# McPiFace-60mmFan-V1.net
KiCad netlist of a schematic drawn in EAGLE
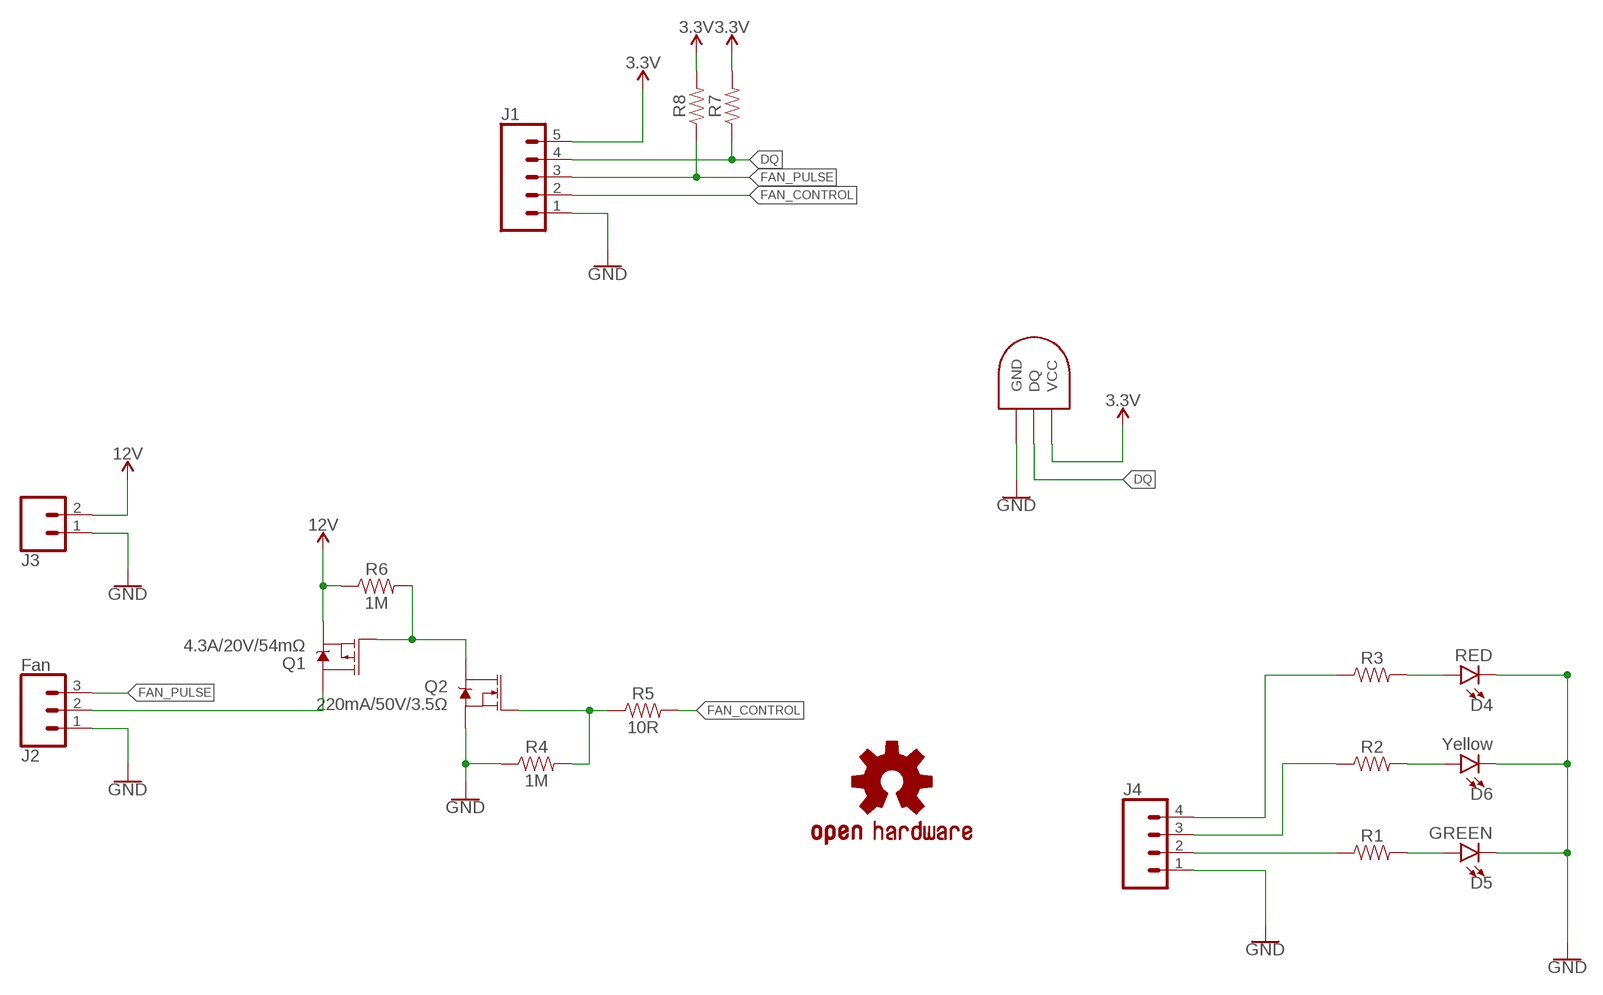
[diagram p0: schematic, sheet 1]

(export (version "E")
  (design (tool "Eeschema 10.0.6"))
  (components
    (comp (ref "D4")
      (value "RED")
      (footprint "eagle-import:LED-1206")
      (libsource (lib "eagle-import") (part "LED-RED1206"))
    )
    (comp (ref "D5")
      (value "GREEN")
      (footprint "eagle-import:LED-1206")
      (libsource (lib "eagle-import") (part "LED-GREEN1206"))
    )
    (comp (ref "D6")
      (value "Yellow")
      (footprint "eagle-import:LED-1206")
      (libsource (lib "eagle-import") (part "LED-YELLOWLILYPAD"))
    )
    (comp (ref "J1")
      (value "CONN_05SMD")
      (footprint "eagle-import:1X05_1MM")
      (libsource (lib "eagle-import") (part "CONN_05SMD"))
    )
    (comp (ref "J2")
      (value "Fan")
      (footprint "eagle-import:JST-3-SMD")
      (libsource (lib "eagle-import") (part "CONN_03JST-SMD"))
    )
    (comp (ref "J3")
      (value "CONN_02-JST-2MM-SMT")
      (footprint "eagle-import:JST-2-SMD")
      (libsource (lib "eagle-import") (part "CONN_02-JST-2MM-SMT"))
    )
    (comp (ref "J4")
      (value "CONN_04SMD2")
      (footprint "eagle-import:1X04_1MM_RA")
      (libsource (lib "eagle-import") (part "CONN_04SMD2"))
    )
    (comp (ref "LOGO1")
      (value "OSHW-LOGOL")
      (footprint "eagle-import:OSHW-LOGO-L")
      (libsource (lib "eagle-import") (part "OSHW-LOGOL"))
    )
    (comp (ref "Q1")
      (value "4.3A/20V/54mΩ")
      (footprint "eagle-import:SOT23-3")
      (libsource (lib "eagle-import") (part "MOSFET_PCH-IRLML2244"))
    )
    (comp (ref "Q2")
      (value "220mA/50V/3.5Ω")
      (footprint "eagle-import:SOT23-3")
      (libsource (lib "eagle-import") (part "MOSFET-NCH-BSS138"))
    )
    (comp (ref "R1")
      (value "RESISTOR1206")
      (footprint "eagle-import:1206")
      (libsource (lib "eagle-import") (part "RESISTOR1206"))
    )
    (comp (ref "R2")
      (value "RESISTOR1206")
      (footprint "eagle-import:1206")
      (libsource (lib "eagle-import") (part "RESISTOR1206"))
    )
    (comp (ref "R3")
      (value "RESISTOR1206")
      (footprint "eagle-import:1206")
      (libsource (lib "eagle-import") (part "RESISTOR1206"))
    )
    (comp (ref "R4")
      (value "1M")
      (footprint "eagle-import:0805")
      (libsource (lib "eagle-import") (part "RESISTOR0805"))
    )
    (comp (ref "R5")
      (value "10R")
      (footprint "eagle-import:0805")
      (libsource (lib "eagle-import") (part "RESISTOR0805"))
    )
    (comp (ref "R6")
      (value "1M")
      (footprint "eagle-import:0805")
      (libsource (lib "eagle-import") (part "RESISTOR0805"))
    )
    (comp (ref "R7")
      (value "RESISTOR0805")
      (footprint "eagle-import:0805")
      (libsource (lib "eagle-import") (part "RESISTOR0805"))
    )
    (comp (ref "R8")
      (value "RESISTOR0805")
      (footprint "eagle-import:0805")
      (libsource (lib "eagle-import") (part "RESISTOR0805"))
    )
    (comp (ref "U$1")
      (value "DS1820SOIC")
      (footprint "eagle-import:DS18B20_SOIC")
      (libsource (lib "eagle-import") (part "DS1820SOIC"))
    )
  )
  (nets
    (net (code "1") (name "3.3V") (class "Default")
      (node (ref "J1") (pin "5") (pinfunction "5_5") (pintype "passive"))
      (node (ref "R7") (pin "2") (pinfunction "2_2") (pintype "passive"))
      (node (ref "R8") (pin "2") (pinfunction "2_2") (pintype "passive"))
      (node (ref "U$1") (pin "VCC") (pinfunction "VCC_VCC") (pintype "power_in"))
    )
    (net (code "2") (name "12V") (class "Default")
      (node (ref "J3") (pin "2") (pinfunction "1_2") (pintype "passive"))
      (node (ref "Q1") (pin "2") (pinfunction "S_2") (pintype "bidirectional"))
      (node (ref "R6") (pin "1") (pinfunction "1_1") (pintype "passive"))
    )
    (net (code "3") (name "DQ") (class "Default")
      (node (ref "J1") (pin "4") (pinfunction "4_4") (pintype "passive"))
      (node (ref "R7") (pin "1") (pinfunction "1_1") (pintype "passive"))
      (node (ref "U$1") (pin "DQ") (pinfunction "DQ_DQ") (pintype "bidirectional"))
    )
    (net (code "4") (name "FAN_CONTROL") (class "Default")
      (node (ref "J1") (pin "2") (pinfunction "2_2") (pintype "passive"))
      (node (ref "R5") (pin "2") (pinfunction "2_2") (pintype "passive"))
    )
    (net (code "5") (name "FAN_PULSE") (class "Default")
      (node (ref "J1") (pin "3") (pinfunction "3_3") (pintype "passive"))
      (node (ref "J2") (pin "3") (pinfunction "1_3") (pintype "passive"))
      (node (ref "R8") (pin "1") (pinfunction "1_1") (pintype "passive"))
    )
    (net (code "6") (name "GND") (class "Default")
      (node (ref "D4") (pin "C") (pinfunction "C_C") (pintype "passive"))
      (node (ref "D5") (pin "C") (pinfunction "C_C") (pintype "passive"))
      (node (ref "D6") (pin "C") (pinfunction "C_C") (pintype "passive"))
      (node (ref "J1") (pin "1") (pinfunction "1_1") (pintype "passive"))
      (node (ref "J2") (pin "1") (pinfunction "3_1") (pintype "passive"))
      (node (ref "J3") (pin "1") (pinfunction "2_1") (pintype "passive"))
      (node (ref "J4") (pin "1") (pinfunction "1_1") (pintype "passive"))
      (node (ref "Q2") (pin "2") (pinfunction "S_2") (pintype "bidirectional"))
      (node (ref "R4") (pin "1") (pinfunction "1_1") (pintype "passive"))
      (node (ref "U$1") (pin "GND") (pinfunction "GND_GND") (pintype "power_in"))
    )
    (net (code "7") (name "Net-(D4-PadA)") (class "Default")
      (node (ref "D4") (pin "A") (pinfunction "A_A") (pintype "passive"))
      (node (ref "R3") (pin "2") (pinfunction "2_2") (pintype "passive"))
    )
    (net (code "8") (name "Net-(D5-PadA)") (class "Default")
      (node (ref "D5") (pin "A") (pinfunction "A_A") (pintype "passive"))
      (node (ref "R1") (pin "2") (pinfunction "2_2") (pintype "passive"))
    )
    (net (code "9") (name "Net-(D6-PadA)") (class "Default")
      (node (ref "D6") (pin "A") (pinfunction "A_A") (pintype "passive"))
      (node (ref "R2") (pin "2") (pinfunction "2_2") (pintype "passive"))
    )
    (net (code "10") (name "Net-(J4-Pad2)") (class "Default")
      (node (ref "J4") (pin "2") (pinfunction "2_2") (pintype "passive"))
      (node (ref "R1") (pin "1") (pinfunction "1_1") (pintype "passive"))
    )
    (net (code "11") (name "Net-(J4-Pad3)") (class "Default")
      (node (ref "J4") (pin "3") (pinfunction "3_3") (pintype "passive"))
      (node (ref "R2") (pin "1") (pinfunction "1_1") (pintype "passive"))
    )
    (net (code "12") (name "Net-(J4-Pad4)") (class "Default")
      (node (ref "J4") (pin "4") (pinfunction "4_4") (pintype "passive"))
      (node (ref "R3") (pin "1") (pinfunction "1_1") (pintype "passive"))
    )
    (net (code "13") (name "Net-(Q1-D)") (class "Default")
      (node (ref "J2") (pin "2") (pinfunction "2_2") (pintype "passive"))
      (node (ref "Q1") (pin "3") (pinfunction "D_3") (pintype "bidirectional"))
    )
    (net (code "14") (name "Net-(Q1-G)") (class "Default")
      (node (ref "Q1") (pin "1") (pinfunction "G_1") (pintype "bidirectional"))
      (node (ref "Q2") (pin "3") (pinfunction "D_3") (pintype "bidirectional"))
      (node (ref "R6") (pin "2") (pinfunction "2_2") (pintype "passive"))
    )
    (net (code "15") (name "Net-(Q2-G)") (class "Default")
      (node (ref "Q2") (pin "1") (pinfunction "G_1") (pintype "bidirectional"))
      (node (ref "R4") (pin "2") (pinfunction "2_2") (pintype "passive"))
      (node (ref "R5") (pin "1") (pinfunction "1_1") (pintype "passive"))
    )
  )
)
